# Motor_Driver_IR2184_Board_V1_0.net
KiCad netlist of a schematic drawn in Altium Designer
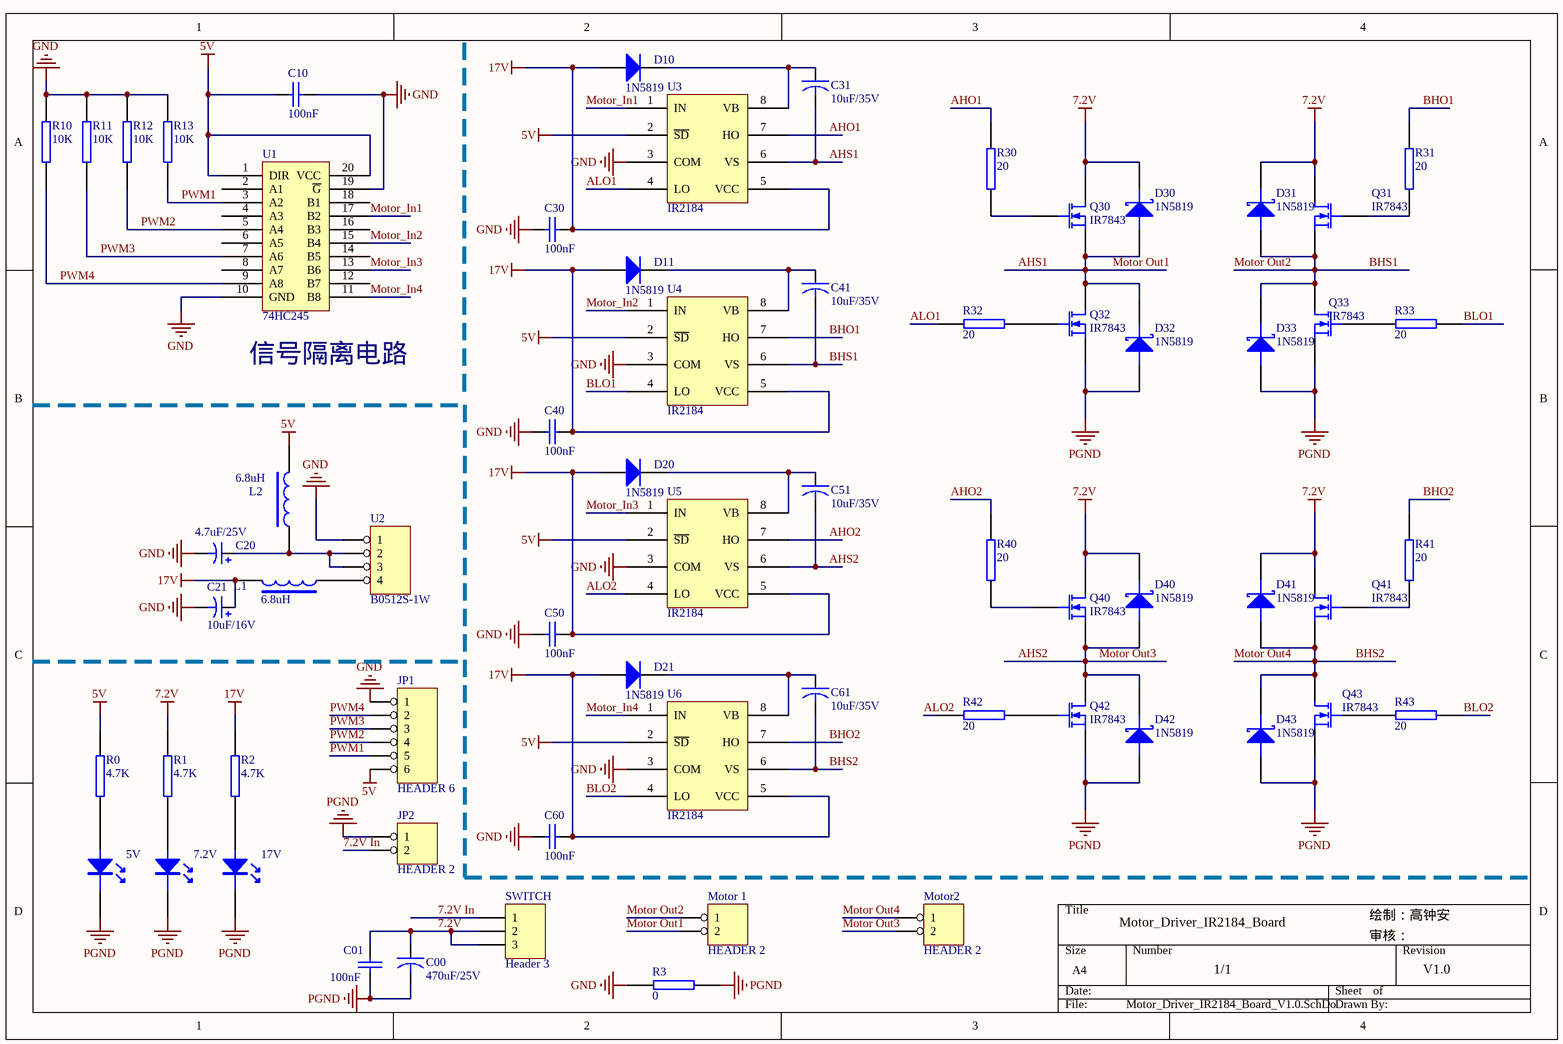
[diagram p0: Motor_Driver_IR2184_Board_V1.0.SchDoc]

(export (version "E")
  (design (tool "Eeschema 10.0.6"))
  (components
    (comp (ref "5V") (value "~") (footprint "0805_LED_S1") (libsource (lib "Protel99Lib_SCH") (part "LED")))
    (comp (ref "7.2V") (value "~") (footprint "0805_LED_S1") (libsource (lib "Protel99Lib_SCH") (part "LED")))
    (comp (ref "17V") (value "~") (footprint "0805_LED_S1") (libsource (lib "Protel99Lib_SCH") (part "LED")))
    (comp (ref "C00")
      (value "470uF/25V")
      (footprint "RB.2/.4")
      (description "Capacitor")
      (libsource (lib "Protel99Lib_SCH") (part "CAPACITOR"))
    )
    (comp (ref "C01")
      (value "100nF")
      (footprint "0805C")
      (description "Capacitor")
      (libsource (lib "Protel99Lib_SCH") (part "CAP"))
    )
    (comp (ref "C10")
      (value "100nF")
      (footprint "0805C")
      (description "Capacitor")
      (libsource (lib "Protel99Lib_SCH") (part "CAP"))
    )
    (comp (ref "C20")
      (value "4.7uF/25V")
      (footprint "3528")
      (description "Polarized Capacitor (Surface Mount)")
      (fields (field (name "PUBLISHER") "Altium Limited"))
      (libsource (lib "Miscellaneous Devices") (part "Cap Pol3"))
    )
    (comp (ref "C21")
      (value "10uF/16V")
      (footprint "3528")
      (description "Polarized Capacitor (Surface Mount)")
      (fields (field (name "PUBLISHER") "Altium Limited"))
      (libsource (lib "Miscellaneous Devices") (part "Cap Pol3"))
    )
    (comp (ref "C30")
      (value "100nF")
      (footprint "0805C")
      (description "Capacitor")
      (libsource (lib "Motor_Driver_IR2184") (part "CAP"))
    )
    (comp (ref "C31")
      (value "10uF/35V")
      (footprint "3528")
      (description "Capacitor")
      (libsource (lib "Motor_Driver_IR2184") (part "CAPACITOR"))
    )
    (comp (ref "C40")
      (value "100nF")
      (footprint "0805C")
      (description "Capacitor")
      (libsource (lib "Motor_Driver_IR2184") (part "CAP"))
    )
    (comp (ref "C41")
      (value "10uF/35V")
      (footprint "3528")
      (description "Capacitor")
      (libsource (lib "Motor_Driver_IR2184") (part "CAPACITOR"))
    )
    (comp (ref "C50")
      (value "100nF")
      (footprint "0805C")
      (description "Capacitor")
      (libsource (lib "Motor_Driver_IR2184") (part "CAP"))
    )
    (comp (ref "C51")
      (value "10uF/35V")
      (footprint "3528")
      (description "Capacitor")
      (libsource (lib "Motor_Driver_IR2184") (part "CAPACITOR"))
    )
    (comp (ref "C60")
      (value "100nF")
      (footprint "0805C")
      (description "Capacitor")
      (libsource (lib "Motor_Driver_IR2184") (part "CAP"))
    )
    (comp (ref "C61")
      (value "10uF/35V")
      (footprint "3528")
      (description "Capacitor")
      (libsource (lib "Motor_Driver_IR2184") (part "CAPACITOR"))
    )
    (comp (ref "D10")
      (value "1N5819")
      (footprint "SOD-323")
      (description "Default Diode")
      (fields (field (name "PUBLISHER") "Altium Limited"))
      (libsource (lib "Motor_Driver_IR2184") (part "Diode"))
    )
    (comp (ref "D11")
      (value "1N5819")
      (footprint "SOD-323")
      (description "Default Diode")
      (fields (field (name "PUBLISHER") "Altium Limited"))
      (libsource (lib "Motor_Driver_IR2184") (part "Diode"))
    )
    (comp (ref "D20")
      (value "1N5819")
      (footprint "SOD-323")
      (description "Default Diode")
      (fields (field (name "PUBLISHER") "Altium Limited"))
      (libsource (lib "Motor_Driver_IR2184") (part "Diode"))
    )
    (comp (ref "D21")
      (value "1N5819")
      (footprint "SOD-323")
      (description "Default Diode")
      (fields (field (name "PUBLISHER") "Altium Limited"))
      (libsource (lib "Motor_Driver_IR2184") (part "Diode"))
    )
    (comp (ref "D30")
      (value "1N5819")
      (footprint "SOD-323")
      (description "Schottky Diode")
      (libsource (lib "Protel99Lib_SCH") (part "DIODE SCHOTTKY"))
    )
    (comp (ref "D31")
      (value "1N5819")
      (footprint "SOD-323")
      (description "Schottky Diode")
      (libsource (lib "Protel99Lib_SCH") (part "DIODE SCHOTTKY"))
    )
    (comp (ref "D32")
      (value "1N5819")
      (footprint "SOD-323")
      (description "Schottky Diode")
      (libsource (lib "Protel99Lib_SCH") (part "DIODE SCHOTTKY"))
    )
    (comp (ref "D33")
      (value "1N5819")
      (footprint "SOD-323")
      (description "Schottky Diode")
      (libsource (lib "Protel99Lib_SCH") (part "DIODE SCHOTTKY"))
    )
    (comp (ref "D40")
      (value "1N5819")
      (footprint "SOD-323")
      (description "Schottky Diode")
      (libsource (lib "Protel99Lib_SCH") (part "DIODE SCHOTTKY"))
    )
    (comp (ref "D41")
      (value "1N5819")
      (footprint "SOD-323")
      (description "Schottky Diode")
      (libsource (lib "Protel99Lib_SCH") (part "DIODE SCHOTTKY"))
    )
    (comp (ref "D42")
      (value "1N5819")
      (footprint "SOD-323")
      (description "Schottky Diode")
      (libsource (lib "Protel99Lib_SCH") (part "DIODE SCHOTTKY"))
    )
    (comp (ref "D43")
      (value "1N5819")
      (footprint "SOD-323")
      (description "Schottky Diode")
      (libsource (lib "Protel99Lib_SCH") (part "DIODE SCHOTTKY"))
    )
    (comp (ref "JP1")
      (value "HEADER 6")
      (footprint "SIP6N")
      (libsource (lib "Protel99Lib_SCH") (part "HEADER 6"))
    )
    (comp (ref "JP2")
      (value "HEADER 2")
      (footprint "KF301-2P")
      (libsource (lib "Protel99Lib_SCH") (part "HEADER 2"))
    )
    (comp (ref "L1")
      (value "6.8uH")
      (footprint "1206_L")
      (libsource (lib "Protel99Lib_SCH") (part "INDUCTOR2"))
    )
    (comp (ref "L2") (value "6.8uH") (footprint "1206_L") (libsource (lib "") (part "INDUCTOR2_1")))
    (comp (ref "Motor 1")
      (value "HEADER 2")
      (footprint "KF301-2P")
      (libsource (lib "Protel99Lib_SCH") (part "HEADER 2"))
    )
    (comp (ref "Motor2")
      (value "HEADER 2")
      (footprint "KF301-2P")
      (libsource (lib "Protel99Lib_SCH") (part "HEADER 2"))
    )
    (comp (ref "Q30")
      (value "IR7843")
      (footprint "LR7843")
      (description "N-Channel MOSFET")
      (fields (field (name "PUBLISHER") "Altium Limited"))
      (libsource (lib "Miscellaneous Devices") (part "MOSFET-N"))
    )
    (comp (ref "Q31")
      (value "IR7843")
      (footprint "LR7843")
      (description "N-Channel MOSFET")
      (fields (field (name "PUBLISHER") "Altium Limited"))
      (libsource (lib "Miscellaneous Devices") (part "MOSFET-N"))
    )
    (comp (ref "Q32")
      (value "IR7843")
      (footprint "LR7843")
      (description "N-Channel MOSFET")
      (fields (field (name "PUBLISHER") "Altium Limited"))
      (libsource (lib "Miscellaneous Devices") (part "MOSFET-N"))
    )
    (comp (ref "Q33")
      (value "IR7843")
      (footprint "LR7843")
      (description "N-Channel MOSFET")
      (fields (field (name "PUBLISHER") "Altium Limited"))
      (libsource (lib "Miscellaneous Devices") (part "MOSFET-N"))
    )
    (comp (ref "Q40")
      (value "IR7843")
      (footprint "LR7843")
      (description "N-Channel MOSFET")
      (fields (field (name "PUBLISHER") "Altium Limited"))
      (libsource (lib "Miscellaneous Devices") (part "MOSFET-N"))
    )
    (comp (ref "Q41")
      (value "IR7843")
      (footprint "LR7843")
      (description "N-Channel MOSFET")
      (fields (field (name "PUBLISHER") "Altium Limited"))
      (libsource (lib "Miscellaneous Devices") (part "MOSFET-N"))
    )
    (comp (ref "Q42")
      (value "IR7843")
      (footprint "LR7843")
      (description "N-Channel MOSFET")
      (fields (field (name "PUBLISHER") "Altium Limited"))
      (libsource (lib "Miscellaneous Devices") (part "MOSFET-N"))
    )
    (comp (ref "Q43")
      (value "IR7843")
      (footprint "LR7843")
      (description "N-Channel MOSFET")
      (fields (field (name "PUBLISHER") "Altium Limited"))
      (libsource (lib "Miscellaneous Devices") (part "MOSFET-N"))
    )
    (comp (ref "R0") (value "4.7K") (footprint "0603_R") (libsource (lib "Protel99Lib_SCH") (part "RES2")))
    (comp (ref "R1") (value "4.7K") (footprint "0603_R") (libsource (lib "Protel99Lib_SCH") (part "RES2")))
    (comp (ref "R2") (value "4.7K") (footprint "0603_R") (libsource (lib "Protel99Lib_SCH") (part "RES2")))
    (comp (ref "R3") (value "0") (footprint "0805R") (libsource (lib "Protel99Lib_SCH") (part "RES2")))
    (comp (ref "R10") (value "10K") (footprint "0603_R") (libsource (lib "") (part "RES2_1")))
    (comp (ref "R11") (value "10K") (footprint "0603_R") (libsource (lib "") (part "RES2_1")))
    (comp (ref "R12") (value "10K") (footprint "0603_R") (libsource (lib "") (part "RES2_1")))
    (comp (ref "R13") (value "10K") (footprint "0603_R") (libsource (lib "") (part "RES2_1")))
    (comp (ref "R30") (value "20") (footprint "0805") (libsource (lib "Protel99Lib_SCH") (part "RES2")))
    (comp (ref "R31") (value "20") (footprint "0805") (libsource (lib "Protel99Lib_SCH") (part "RES2")))
    (comp (ref "R32") (value "20") (footprint "0805") (libsource (lib "Protel99Lib_SCH") (part "RES2")))
    (comp (ref "R33") (value "20") (footprint "0805") (libsource (lib "Protel99Lib_SCH") (part "RES2")))
    (comp (ref "R40") (value "20") (footprint "0805") (libsource (lib "Protel99Lib_SCH") (part "RES2")))
    (comp (ref "R41") (value "20") (footprint "0805") (libsource (lib "Protel99Lib_SCH") (part "RES2")))
    (comp (ref "R42") (value "20") (footprint "0805") (libsource (lib "Protel99Lib_SCH") (part "RES2")))
    (comp (ref "R43") (value "20") (footprint "0805") (libsource (lib "Protel99Lib_SCH") (part "RES2")))
    (comp (ref "SWITCH")
      (value "Header 3")
      (footprint "KEY-3P")
      (description "Header, 3-Pin")
      (fields (field (name "PUBLISHER") "Altium Limited"))
      (libsource (lib "Miscellaneous Connectors") (part "Header 3"))
    )
    (comp (ref "U1") (value "74HC245") (footprint "SOP20") (libsource (lib "BaseLib_SCH") (part "74HC245")))
    (comp (ref "U2")
      (value "B0512S-1W")
      (footprint "SIP4_B_S-1W")
      (description "4 Pin Header")
      (libsource (lib "Protel99Lib_SCH") (part "4 HEADER"))
    )
    (comp (ref "U3") (value "IR2184") (footprint "SO-8") (libsource (lib "GD32") (part "IR2184")))
    (comp (ref "U4") (value "IR2184") (footprint "SO-8") (libsource (lib "GD32") (part "IR2184")))
    (comp (ref "U5") (value "IR2184") (footprint "SO-8") (libsource (lib "GD32") (part "IR2184")))
    (comp (ref "U6") (value "IR2184") (footprint "SO-8") (libsource (lib "GD32") (part "IR2184")))
  )
  (nets
    (net (code "1") (name "/7.2V In") (class "Default")
      (node (ref "JP2") (pin "2") (pinfunction "2_2") (pintype "passive"))
      (node (ref "SWITCH") (pin "1") (pinfunction "1_1") (pintype "passive"))
    )
    (net (code "2") (name "/AHO1") (class "Default")
      (node (ref "R30") (pin "2") (pinfunction "2_2") (pintype "passive"))
      (node (ref "U3") (pin "7") (pinfunction "HO_7") (pintype "passive"))
    )
    (net (code "3") (name "/AHO2") (class "Default")
      (node (ref "R40") (pin "2") (pinfunction "2_2") (pintype "passive"))
      (node (ref "U5") (pin "7") (pinfunction "HO_7") (pintype "passive"))
    )
    (net (code "4") (name "/AHS1") (class "Default")
      (node (ref "C31") (pin "2") (pinfunction "2_2") (pintype "passive"))
      (node (ref "D30") (pin "1") (pinfunction "A_1") (pintype "passive"))
      (node (ref "D32") (pin "2") (pinfunction "K_2") (pintype "passive"))
      (node (ref "Motor 1") (pin "2") (pinfunction "2_2") (pintype "passive"))
      (node (ref "Q30") (pin "3") (pinfunction "S_3") (pintype "passive"))
      (node (ref "Q32") (pin "1") (pinfunction "D_1") (pintype "passive"))
      (node (ref "U3") (pin "6") (pinfunction "VS_6") (pintype "passive"))
    )
    (net (code "5") (name "/AHS2") (class "Default")
      (node (ref "C51") (pin "2") (pinfunction "2_2") (pintype "passive"))
      (node (ref "D40") (pin "1") (pinfunction "A_1") (pintype "passive"))
      (node (ref "D42") (pin "2") (pinfunction "K_2") (pintype "passive"))
      (node (ref "Motor2") (pin "2") (pinfunction "2_2") (pintype "passive"))
      (node (ref "Q40") (pin "3") (pinfunction "S_3") (pintype "passive"))
      (node (ref "Q42") (pin "1") (pinfunction "D_1") (pintype "passive"))
      (node (ref "U5") (pin "6") (pinfunction "VS_6") (pintype "passive"))
    )
    (net (code "6") (name "/ALO1") (class "Default")
      (node (ref "R32") (pin "2") (pinfunction "2_2") (pintype "passive"))
      (node (ref "U3") (pin "4") (pinfunction "LO_4") (pintype "passive"))
    )
    (net (code "7") (name "/ALO2") (class "Default")
      (node (ref "R42") (pin "2") (pinfunction "2_2") (pintype "passive"))
      (node (ref "U5") (pin "4") (pinfunction "LO_4") (pintype "passive"))
    )
    (net (code "8") (name "/BHO1") (class "Default")
      (node (ref "R31") (pin "2") (pinfunction "2_2") (pintype "passive"))
      (node (ref "U4") (pin "7") (pinfunction "HO_7") (pintype "passive"))
    )
    (net (code "9") (name "/BHO2") (class "Default")
      (node (ref "R41") (pin "2") (pinfunction "2_2") (pintype "passive"))
      (node (ref "U6") (pin "7") (pinfunction "HO_7") (pintype "passive"))
    )
    (net (code "10") (name "/BHS1") (class "Default")
      (node (ref "C41") (pin "2") (pinfunction "2_2") (pintype "passive"))
      (node (ref "D31") (pin "1") (pinfunction "A_1") (pintype "passive"))
      (node (ref "D33") (pin "2") (pinfunction "K_2") (pintype "passive"))
      (node (ref "Motor 1") (pin "1") (pinfunction "1_1") (pintype "passive"))
      (node (ref "Q31") (pin "3") (pinfunction "S_3") (pintype "passive"))
      (node (ref "Q33") (pin "1") (pinfunction "D_1") (pintype "passive"))
      (node (ref "U4") (pin "6") (pinfunction "VS_6") (pintype "passive"))
    )
    (net (code "11") (name "/BHS2") (class "Default")
      (node (ref "C61") (pin "2") (pinfunction "2_2") (pintype "passive"))
      (node (ref "D41") (pin "1") (pinfunction "A_1") (pintype "passive"))
      (node (ref "D43") (pin "2") (pinfunction "K_2") (pintype "passive"))
      (node (ref "Motor2") (pin "1") (pinfunction "1_1") (pintype "passive"))
      (node (ref "Q41") (pin "3") (pinfunction "S_3") (pintype "passive"))
      (node (ref "Q43") (pin "1") (pinfunction "D_1") (pintype "passive"))
      (node (ref "U6") (pin "6") (pinfunction "VS_6") (pintype "passive"))
    )
    (net (code "12") (name "/BLO1") (class "Default")
      (node (ref "R33") (pin "1") (pinfunction "1_1") (pintype "passive"))
      (node (ref "U4") (pin "4") (pinfunction "LO_4") (pintype "passive"))
    )
    (net (code "13") (name "/BLO2") (class "Default")
      (node (ref "R43") (pin "1") (pinfunction "1_1") (pintype "passive"))
      (node (ref "U6") (pin "4") (pinfunction "LO_4") (pintype "passive"))
    )
    (net (code "14") (name "/Motor_In1") (class "Default")
      (node (ref "U1") (pin "17") (pinfunction "B2_17") (pintype "passive"))
      (node (ref "U3") (pin "1") (pinfunction "IN_1") (pintype "passive"))
    )
    (net (code "15") (name "/Motor_In2") (class "Default")
      (node (ref "U1") (pin "15") (pinfunction "B4_15") (pintype "passive"))
      (node (ref "U4") (pin "1") (pinfunction "IN_1") (pintype "passive"))
    )
    (net (code "16") (name "/Motor_In3") (class "Default")
      (node (ref "U1") (pin "13") (pinfunction "B6_13") (pintype "passive"))
      (node (ref "U5") (pin "1") (pinfunction "IN_1") (pintype "passive"))
    )
    (net (code "17") (name "/Motor_In4") (class "Default")
      (node (ref "U1") (pin "11") (pinfunction "B8_11") (pintype "passive"))
      (node (ref "U6") (pin "1") (pinfunction "IN_1") (pintype "passive"))
    )
    (net (code "18") (name "/PWM1") (class "Default")
      (node (ref "JP1") (pin "5") (pinfunction "5_5") (pintype "passive"))
      (node (ref "R13") (pin "1") (pinfunction "1_1") (pintype "passive"))
      (node (ref "U1") (pin "3") (pinfunction "A2_3") (pintype "passive"))
    )
    (net (code "19") (name "/PWM2") (class "Default")
      (node (ref "JP1") (pin "4") (pinfunction "4_4") (pintype "passive"))
      (node (ref "R12") (pin "1") (pinfunction "1_1") (pintype "passive"))
      (node (ref "U1") (pin "5") (pinfunction "A4_5") (pintype "passive"))
    )
    (net (code "20") (name "/PWM3") (class "Default")
      (node (ref "JP1") (pin "3") (pinfunction "3_3") (pintype "passive"))
      (node (ref "R11") (pin "2") (pinfunction "2_2") (pintype "passive"))
      (node (ref "U1") (pin "7") (pinfunction "A6_7") (pintype "passive"))
    )
    (net (code "21") (name "/PWM4") (class "Default")
      (node (ref "JP1") (pin "2") (pinfunction "2_2") (pintype "passive"))
      (node (ref "R10") (pin "1") (pinfunction "1_1") (pintype "passive"))
      (node (ref "U1") (pin "9") (pinfunction "A8_9") (pintype "passive"))
    )
    (net (code "22") (name "5V") (class "Default")
      (node (ref "C10") (pin "1") (pinfunction "1_1") (pintype "passive"))
      (node (ref "JP1") (pin "6") (pinfunction "6_6") (pintype "passive"))
      (node (ref "L2") (pin "2") (pinfunction "2_2") (pintype "passive"))
      (node (ref "R0") (pin "2") (pinfunction "2_2") (pintype "passive"))
      (node (ref "U1") (pin "1") (pinfunction "DIR_1") (pintype "passive"))
      (node (ref "U1") (pin "20") (pinfunction "VCC_20") (pintype "passive"))
      (node (ref "U3") (pin "2") (pinfunction "~{SD}_2") (pintype "passive"))
      (node (ref "U4") (pin "2") (pinfunction "~{SD}_2") (pintype "passive"))
      (node (ref "U5") (pin "2") (pinfunction "~{SD}_2") (pintype "passive"))
      (node (ref "U6") (pin "2") (pinfunction "~{SD}_2") (pintype "passive"))
    )
    (net (code "23") (name "7.2V") (class "Default")
      (node (ref "C00") (pin "1") (pinfunction "1_1") (pintype "passive"))
      (node (ref "C01") (pin "2") (pinfunction "2_2") (pintype "passive"))
      (node (ref "D30") (pin "2") (pinfunction "K_2") (pintype "passive"))
      (node (ref "D31") (pin "2") (pinfunction "K_2") (pintype "passive"))
      (node (ref "D40") (pin "2") (pinfunction "K_2") (pintype "passive"))
      (node (ref "D41") (pin "2") (pinfunction "K_2") (pintype "passive"))
      (node (ref "Q30") (pin "1") (pinfunction "D_1") (pintype "passive"))
      (node (ref "Q31") (pin "1") (pinfunction "D_1") (pintype "passive"))
      (node (ref "Q40") (pin "1") (pinfunction "D_1") (pintype "passive"))
      (node (ref "Q41") (pin "1") (pinfunction "D_1") (pintype "passive"))
      (node (ref "R1") (pin "2") (pinfunction "2_2") (pintype "passive"))
      (node (ref "SWITCH") (pin "2") (pinfunction "2_2") (pintype "passive"))
      (node (ref "SWITCH") (pin "3") (pinfunction "3_3") (pintype "passive"))
    )
    (net (code "24") (name "17V") (class "Default")
      (node (ref "C21") (pin "1") (pinfunction "1_1") (pintype "passive"))
      (node (ref "C30") (pin "1") (pinfunction "1_1") (pintype "passive"))
      (node (ref "C40") (pin "1") (pinfunction "1_1") (pintype "passive"))
      (node (ref "C50") (pin "1") (pinfunction "1_1") (pintype "passive"))
      (node (ref "C60") (pin "1") (pinfunction "1_1") (pintype "passive"))
      (node (ref "D10") (pin "1") (pinfunction "A_1") (pintype "passive"))
      (node (ref "D11") (pin "1") (pinfunction "A_1") (pintype "passive"))
      (node (ref "D20") (pin "1") (pinfunction "A_1") (pintype "passive"))
      (node (ref "D21") (pin "1") (pinfunction "A_1") (pintype "passive"))
      (node (ref "L1") (pin "2") (pinfunction "2_2") (pintype "passive"))
      (node (ref "R2") (pin "2") (pinfunction "2_2") (pintype "passive"))
      (node (ref "U3") (pin "5") (pinfunction "VCC_5") (pintype "passive"))
      (node (ref "U4") (pin "5") (pinfunction "VCC_5") (pintype "passive"))
      (node (ref "U5") (pin "5") (pinfunction "VCC_5") (pintype "passive"))
      (node (ref "U6") (pin "5") (pinfunction "VCC_5") (pintype "passive"))
    )
    (net (code "25") (name "GND") (class "Default")
      (node (ref "C10") (pin "2") (pinfunction "2_2") (pintype "passive"))
      (node (ref "C20") (pin "2") (pinfunction "2_2") (pintype "passive"))
      (node (ref "C21") (pin "2") (pinfunction "2_2") (pintype "passive"))
      (node (ref "C30") (pin "2") (pinfunction "2_2") (pintype "passive"))
      (node (ref "C40") (pin "2") (pinfunction "2_2") (pintype "passive"))
      (node (ref "C50") (pin "2") (pinfunction "2_2") (pintype "passive"))
      (node (ref "C60") (pin "2") (pinfunction "2_2") (pintype "passive"))
      (node (ref "JP1") (pin "1") (pinfunction "1_1") (pintype "passive"))
      (node (ref "R10") (pin "2") (pinfunction "2_2") (pintype "passive"))
      (node (ref "R11") (pin "1") (pinfunction "1_1") (pintype "passive"))
      (node (ref "R12") (pin "2") (pinfunction "2_2") (pintype "passive"))
      (node (ref "R13") (pin "2") (pinfunction "2_2") (pintype "passive"))
      (node (ref "R3") (pin "2") (pinfunction "2_2") (pintype "passive"))
      (node (ref "U1") (pin "10") (pinfunction "GND_10") (pintype "passive"))
      (node (ref "U1") (pin "19") (pinfunction "~{G}_19") (pintype "passive"))
      (node (ref "U2") (pin "1") (pinfunction "1_1") (pintype "passive"))
      (node (ref "U3") (pin "3") (pinfunction "COM_3") (pintype "passive"))
      (node (ref "U4") (pin "3") (pinfunction "COM_3") (pintype "passive"))
      (node (ref "U5") (pin "3") (pinfunction "COM_3") (pintype "passive"))
      (node (ref "U6") (pin "3") (pinfunction "COM_3") (pintype "passive"))
    )
    (net (code "26") (name "Net-(5V-1)") (class "Default")
      (node (ref "5V") (pin "A") (pinfunction "1_A") (pintype "passive"))
      (node (ref "R0") (pin "1") (pinfunction "1_1") (pintype "passive"))
    )
    (net (code "27") (name "Net-(7.2V-1)") (class "Default")
      (node (ref "7.2V") (pin "A") (pinfunction "1_A") (pintype "passive"))
      (node (ref "R1") (pin "1") (pinfunction "1_1") (pintype "passive"))
    )
    (net (code "28") (name "Net-(17V-1)") (class "Default")
      (node (ref "17V") (pin "A") (pinfunction "1_A") (pintype "passive"))
      (node (ref "R2") (pin "1") (pinfunction "1_1") (pintype "passive"))
    )
    (net (code "29") (name "Net-(C20-Pad1)") (class "Default")
      (node (ref "C20") (pin "1") (pinfunction "1_1") (pintype "passive"))
      (node (ref "L2") (pin "1") (pinfunction "1_1") (pintype "passive"))
      (node (ref "U2") (pin "2") (pinfunction "2_2") (pintype "passive"))
      (node (ref "U2") (pin "3") (pinfunction "3_3") (pintype "passive"))
    )
    (net (code "30") (name "Net-(D10-K)") (class "Default")
      (node (ref "C31") (pin "1") (pinfunction "1_1") (pintype "passive"))
      (node (ref "D10") (pin "2") (pinfunction "K_2") (pintype "passive"))
      (node (ref "U3") (pin "8") (pinfunction "VB_8") (pintype "passive"))
    )
    (net (code "31") (name "Net-(D11-K)") (class "Default")
      (node (ref "C41") (pin "1") (pinfunction "1_1") (pintype "passive"))
      (node (ref "D11") (pin "2") (pinfunction "K_2") (pintype "passive"))
      (node (ref "U4") (pin "8") (pinfunction "VB_8") (pintype "passive"))
    )
    (net (code "32") (name "Net-(D20-K)") (class "Default")
      (node (ref "C51") (pin "1") (pinfunction "1_1") (pintype "passive"))
      (node (ref "D20") (pin "2") (pinfunction "K_2") (pintype "passive"))
      (node (ref "U5") (pin "8") (pinfunction "VB_8") (pintype "passive"))
    )
    (net (code "33") (name "Net-(D21-K)") (class "Default")
      (node (ref "C61") (pin "1") (pinfunction "1_1") (pintype "passive"))
      (node (ref "D21") (pin "2") (pinfunction "K_2") (pintype "passive"))
      (node (ref "U6") (pin "8") (pinfunction "VB_8") (pintype "passive"))
    )
    (net (code "34") (name "Net-(L1-Pad1)") (class "Default")
      (node (ref "L1") (pin "1") (pinfunction "1_1") (pintype "passive"))
      (node (ref "U2") (pin "4") (pinfunction "4_4") (pintype "passive"))
    )
    (net (code "35") (name "Net-(Q30-G)") (class "Default")
      (node (ref "Q30") (pin "2") (pinfunction "G_2") (pintype "passive"))
      (node (ref "R30") (pin "1") (pinfunction "1_1") (pintype "passive"))
    )
    (net (code "36") (name "Net-(Q31-G)") (class "Default")
      (node (ref "Q31") (pin "2") (pinfunction "G_2") (pintype "passive"))
      (node (ref "R31") (pin "1") (pinfunction "1_1") (pintype "passive"))
    )
    (net (code "37") (name "Net-(Q32-G)") (class "Default")
      (node (ref "Q32") (pin "2") (pinfunction "G_2") (pintype "passive"))
      (node (ref "R32") (pin "1") (pinfunction "1_1") (pintype "passive"))
    )
    (net (code "38") (name "Net-(Q33-G)") (class "Default")
      (node (ref "Q33") (pin "2") (pinfunction "G_2") (pintype "passive"))
      (node (ref "R33") (pin "2") (pinfunction "2_2") (pintype "passive"))
    )
    (net (code "39") (name "Net-(Q40-G)") (class "Default")
      (node (ref "Q40") (pin "2") (pinfunction "G_2") (pintype "passive"))
      (node (ref "R40") (pin "1") (pinfunction "1_1") (pintype "passive"))
    )
    (net (code "40") (name "Net-(Q41-G)") (class "Default")
      (node (ref "Q41") (pin "2") (pinfunction "G_2") (pintype "passive"))
      (node (ref "R41") (pin "1") (pinfunction "1_1") (pintype "passive"))
    )
    (net (code "41") (name "Net-(Q42-G)") (class "Default")
      (node (ref "Q42") (pin "2") (pinfunction "G_2") (pintype "passive"))
      (node (ref "R42") (pin "1") (pinfunction "1_1") (pintype "passive"))
    )
    (net (code "42") (name "Net-(Q43-G)") (class "Default")
      (node (ref "Q43") (pin "2") (pinfunction "G_2") (pintype "passive"))
      (node (ref "R43") (pin "2") (pinfunction "2_2") (pintype "passive"))
    )
    (net (code "43") (name "PGND") (class "Default")
      (node (ref "17V") (pin "K") (pinfunction "2_K") (pintype "passive"))
      (node (ref "5V") (pin "K") (pinfunction "2_K") (pintype "passive"))
      (node (ref "7.2V") (pin "K") (pinfunction "2_K") (pintype "passive"))
      (node (ref "C00") (pin "2") (pinfunction "2_2") (pintype "passive"))
      (node (ref "C01") (pin "1") (pinfunction "1_1") (pintype "passive"))
      (node (ref "D32") (pin "1") (pinfunction "A_1") (pintype "passive"))
      (node (ref "D33") (pin "1") (pinfunction "A_1") (pintype "passive"))
      (node (ref "D42") (pin "1") (pinfunction "A_1") (pintype "passive"))
      (node (ref "D43") (pin "1") (pinfunction "A_1") (pintype "passive"))
      (node (ref "JP2") (pin "1") (pinfunction "1_1") (pintype "passive"))
      (node (ref "Q32") (pin "3") (pinfunction "S_3") (pintype "passive"))
      (node (ref "Q33") (pin "3") (pinfunction "S_3") (pintype "passive"))
      (node (ref "Q42") (pin "3") (pinfunction "S_3") (pintype "passive"))
      (node (ref "Q43") (pin "3") (pinfunction "S_3") (pintype "passive"))
      (node (ref "R3") (pin "1") (pinfunction "1_1") (pintype "passive"))
    )
    (net (code "44") (name "unconnected-(U1-A1-Pad2)") (class "Default")
      (node (ref "U1") (pin "2") (pinfunction "A1_2") (pintype "passive"))
    )
    (net (code "45") (name "unconnected-(U1-A3-Pad4)") (class "Default")
      (node (ref "U1") (pin "4") (pinfunction "A3_4") (pintype "passive"))
    )
    (net (code "46") (name "unconnected-(U1-A5-Pad6)") (class "Default")
      (node (ref "U1") (pin "6") (pinfunction "A5_6") (pintype "passive"))
    )
    (net (code "47") (name "unconnected-(U1-A7-Pad8)") (class "Default")
      (node (ref "U1") (pin "8") (pinfunction "A7_8") (pintype "passive"))
    )
    (net (code "48") (name "unconnected-(U1-B1-Pad18)") (class "Default")
      (node (ref "U1") (pin "18") (pinfunction "B1_18") (pintype "passive"))
    )
    (net (code "49") (name "unconnected-(U1-B3-Pad16)") (class "Default")
      (node (ref "U1") (pin "16") (pinfunction "B3_16") (pintype "passive"))
    )
    (net (code "50") (name "unconnected-(U1-B5-Pad14)") (class "Default")
      (node (ref "U1") (pin "14") (pinfunction "B5_14") (pintype "passive"))
    )
    (net (code "51") (name "unconnected-(U1-B7-Pad12)") (class "Default")
      (node (ref "U1") (pin "12") (pinfunction "B7_12") (pintype "passive"))
    )
  )
)
